# Main.net
KiCad netlist of a schematic drawn in Altium Designer
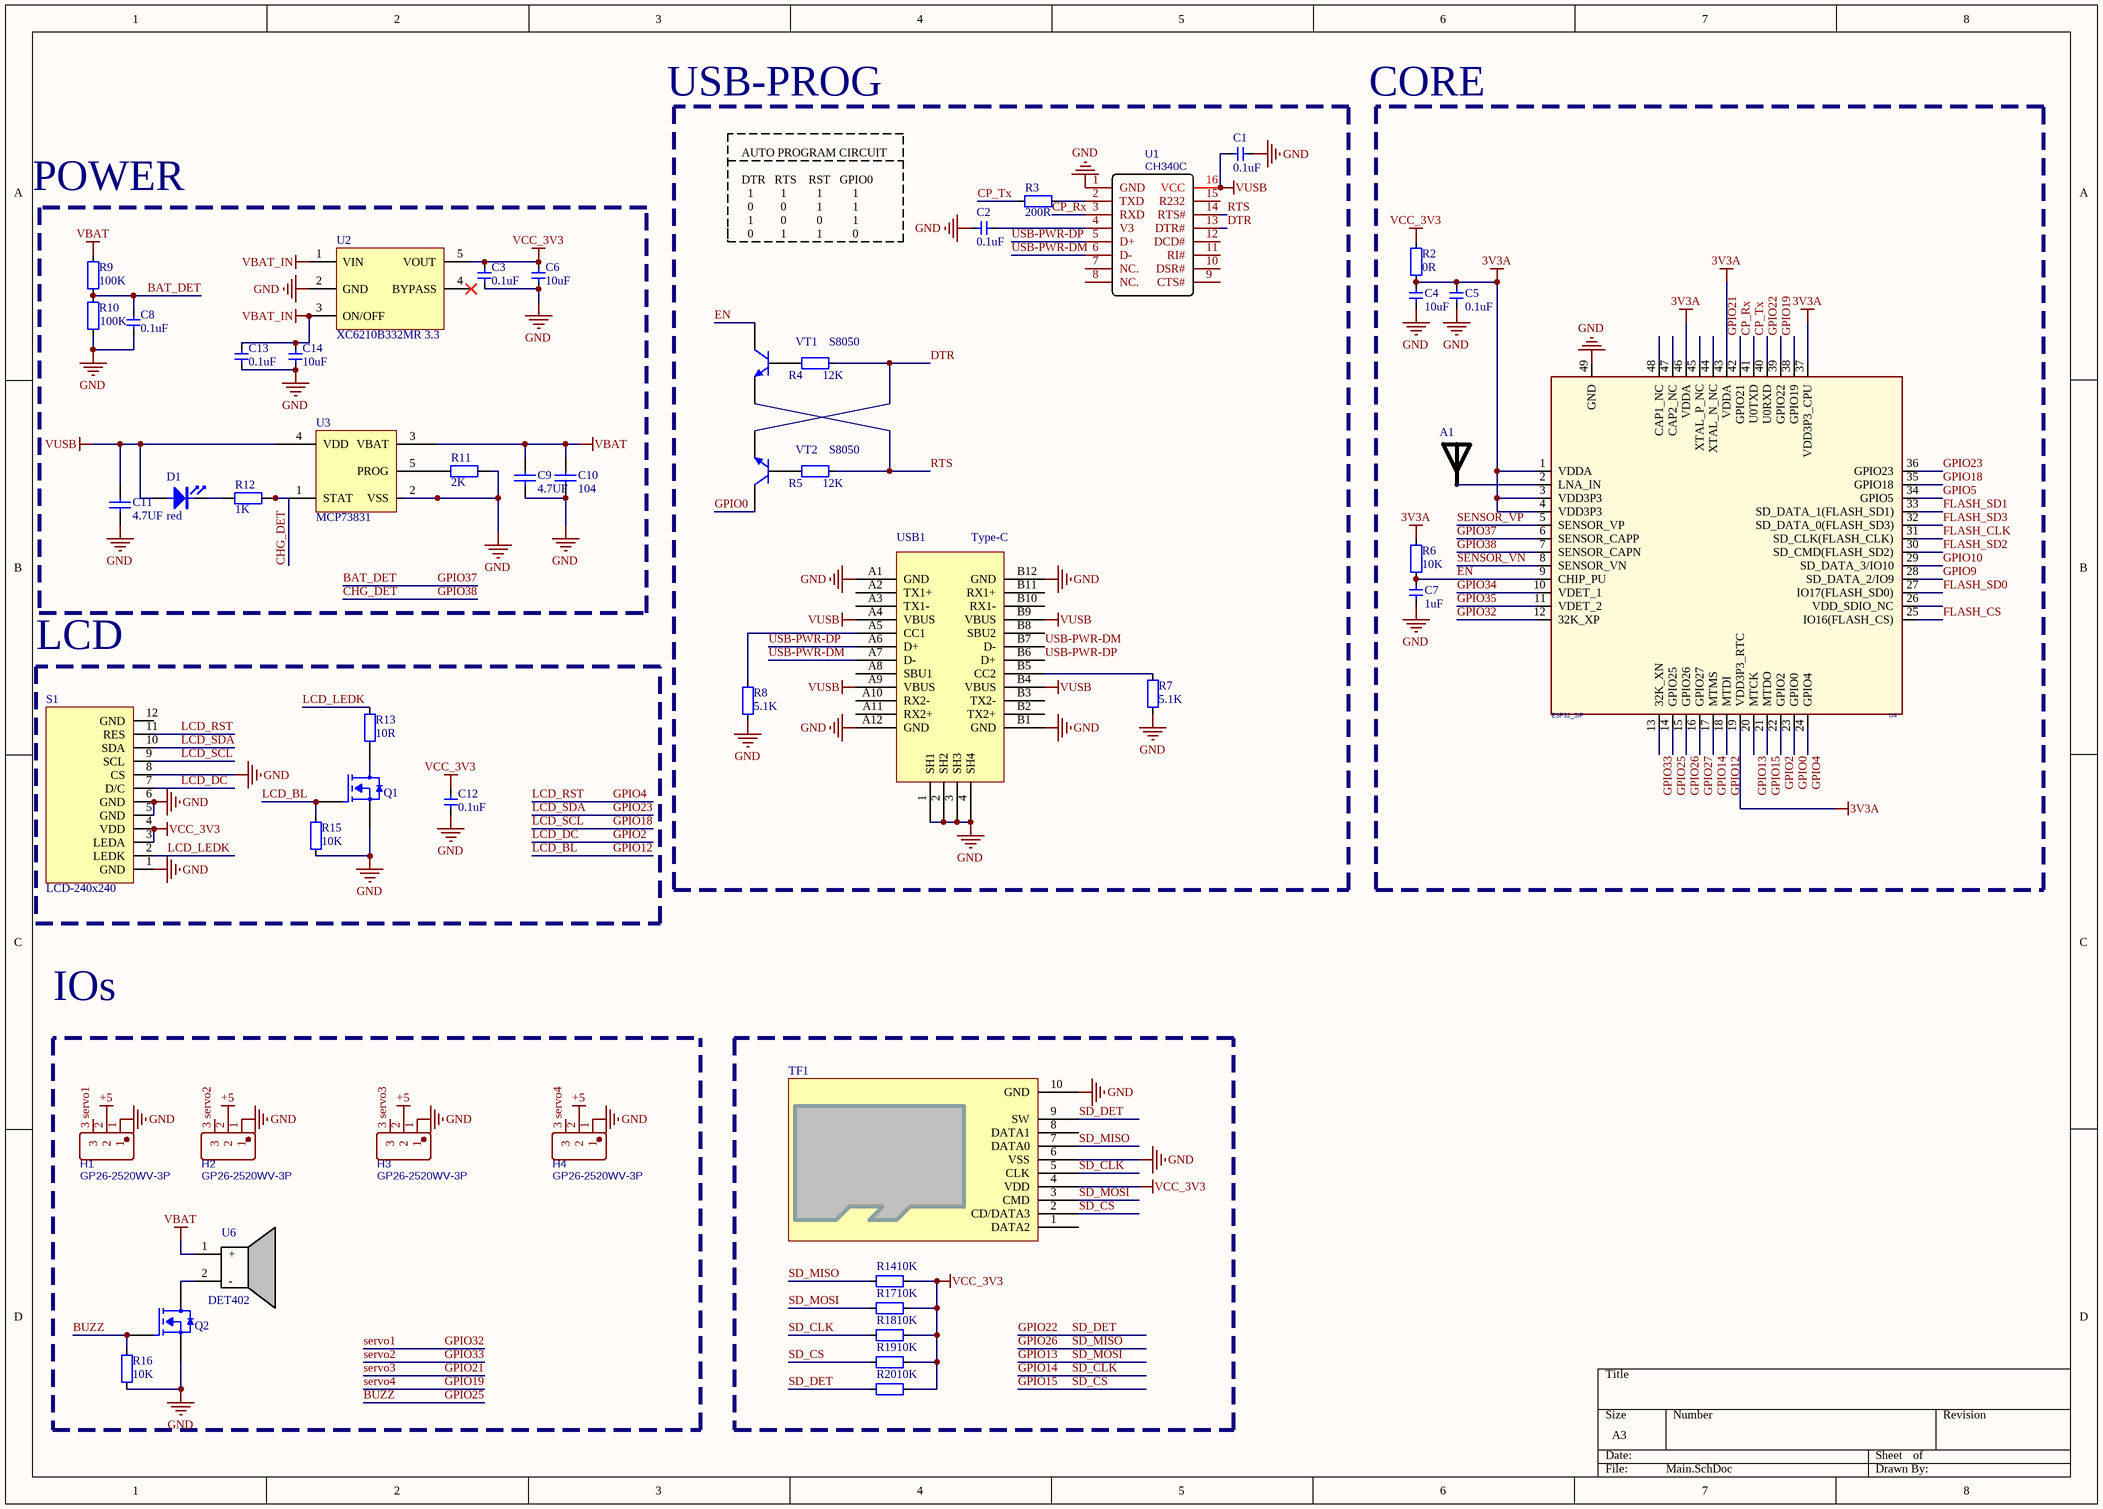
[diagram p0: Main.SchDoc]

(export (version "E")
  (design (tool "Eeschema 10.0.6"))
  (components
    (comp (ref "A1")
      (value "RAINSUN")
      (footprint "otto:ANT-Rainsun-AN5120")
      (libsource (lib "MyPcbLib") (part "ANT-Rainsun-AP5120"))
    )
    (comp (ref "C1")
      (value "0.1uF")
      (footprint "otto:C0603")
      (description "Capacitor")
      (libsource (lib "MyPcbLib") (part "电容-0402"))
    )
    (comp (ref "C2")
      (value "0.1uF")
      (footprint "otto:C0603")
      (description "Capacitor")
      (libsource (lib "MyPcbLib") (part "电容-0402"))
    )
    (comp (ref "C3")
      (value "0.1uF")
      (footprint "otto:C0603")
      (description "Capacitor")
      (libsource (lib "MyPcbLib") (part "电容-0402"))
    )
    (comp (ref "C4")
      (value "10uF")
      (footprint "otto:C0603")
      (description "Capacitor")
      (libsource (lib "MyPcbLib") (part "电容-0402"))
    )
    (comp (ref "C5")
      (value "0.1uF")
      (footprint "otto:C0603")
      (description "Capacitor")
      (libsource (lib "MyPcbLib") (part "电容-0402"))
    )
    (comp (ref "C6")
      (value "10uF")
      (footprint "otto:C0603")
      (description "Capacitor")
      (libsource (lib "MyPcbLib") (part "电容-0402"))
    )
    (comp (ref "C7")
      (value "1uF")
      (footprint "otto:C0603")
      (description "Capacitor")
      (libsource (lib "MyPcbLib") (part "电容-0402"))
    )
    (comp (ref "C8")
      (value "0.1uF")
      (footprint "C0603")
      (description "Capacitor")
      (libsource (lib "OTTO_ESP32") (part "电容-0402"))
    )
    (comp (ref "C9")
      (value "4.7UF")
      (footprint "C0603")
      (fields (field (name "C") "4.7UF"))
      (libsource (lib "元件库") (part "cap"))
    )
    (comp (ref "C10")
      (value "104")
      (footprint "otto:C0603")
      (fields (field (name "C") "104"))
      (libsource (lib "元件库") (part "cap"))
    )
    (comp (ref "C11")
      (value "4.7UF")
      (footprint "C0603")
      (fields (field (name "C") "4.7UF"))
      (libsource (lib "元件库") (part "cap"))
    )
    (comp (ref "C12")
      (value "0.1uF")
      (footprint "otto:C0603")
      (description "Capacitor")
      (libsource (lib "MyPcbLib") (part "电容-0402"))
    )
    (comp (ref "C13")
      (value "0.1uF")
      (footprint "otto:C0603")
      (description "Capacitor")
      (libsource (lib "MyPcbLib") (part "电容-0402"))
    )
    (comp (ref "C14")
      (value "10uF")
      (footprint "otto:C0603")
      (description "Capacitor")
      (libsource (lib "MyPcbLib") (part "电容-0402"))
    )
    (comp (ref "D1") (value "red") (footprint "LED0603") (libsource (lib "元件库") (part "LED")))
    (comp (ref "H1")
      (value "GP26-2520WV-3P")
      (footprint "otto:PIN2.54_1*3")
      (fields (field (name "BOM_SUPPLIER PART") "C2681738") (field (name "CONTRIBUTOR") "LCSC"))
      (libsource (lib "喷雾闹钟") (part "GP26-2520WV-3P"))
    )
    (comp (ref "H2")
      (value "GP26-2520WV-3P")
      (footprint "otto:PIN2.54_1*3")
      (fields (field (name "BOM_SUPPLIER PART") "C2681738") (field (name "CONTRIBUTOR") "LCSC"))
      (libsource (lib "喷雾闹钟") (part "GP26-2520WV-3P"))
    )
    (comp (ref "H3")
      (value "GP26-2520WV-3P")
      (footprint "otto:PIN2.54_1*3")
      (fields (field (name "BOM_SUPPLIER PART") "C2681738") (field (name "CONTRIBUTOR") "LCSC"))
      (libsource (lib "喷雾闹钟") (part "GP26-2520WV-3P"))
    )
    (comp (ref "H4")
      (value "GP26-2520WV-3P")
      (footprint "otto:PIN2.54_1*3")
      (fields (field (name "BOM_SUPPLIER PART") "C2681738") (field (name "CONTRIBUTOR") "LCSC"))
      (libsource (lib "喷雾闹钟") (part "GP26-2520WV-3P"))
    )
    (comp (ref "Q1")
      (value "AO3400A")
      (footprint "otto:SOT23-3")
      (description "N-MOS")
      (libsource (lib "MyPcbLib") (part "AO3400A"))
    )
    (comp (ref "Q2")
      (value "AO3400A")
      (footprint "otto:SOT23-3")
      (description "N-MOS")
      (libsource (lib "MyPcbLib") (part "AO3400A"))
    )
    (comp (ref "R2")
      (value "0R")
      (footprint "otto:R0603")
      (description "Resistor")
      (libsource (lib "OTTO_ESP32") (part "电阻-0402"))
    )
    (comp (ref "R3")
      (value "200R")
      (footprint "otto:R0603")
      (description "Resistor")
      (libsource (lib "") (part "电阻-0402_3"))
    )
    (comp (ref "R4")
      (value "12K")
      (footprint "otto:R0603")
      (description "Resistor")
      (libsource (lib "") (part "电阻-0402_2"))
    )
    (comp (ref "R5")
      (value "12K")
      (footprint "otto:R0603")
      (description "Resistor")
      (libsource (lib "") (part "电阻-0402_2"))
    )
    (comp (ref "R6")
      (value "10K")
      (footprint "otto:R0603")
      (description "Resistor")
      (libsource (lib "OTTO_ESP32") (part "电阻-0402"))
    )
    (comp (ref "R7")
      (value "5.1K")
      (footprint "otto:R0603")
      (description "Resistor")
      (libsource (lib "OTTO_ESP32") (part "电阻-0402"))
    )
    (comp (ref "R8")
      (value "5.1K")
      (footprint "otto:R0603")
      (description "Resistor")
      (libsource (lib "OTTO_ESP32") (part "电阻-0402"))
    )
    (comp (ref "R9")
      (value "100K")
      (footprint "otto:R0603")
      (description "Resistor")
      (libsource (lib "") (part "电阻-0402_1"))
    )
    (comp (ref "R10")
      (value "100K")
      (footprint "otto:R0603")
      (description "Resistor")
      (libsource (lib "") (part "电阻-0402_1"))
    )
    (comp (ref "R11")
      (value "2K")
      (footprint "otto:R0603")
      (fields (field (name "R") "2K"))
      (libsource (lib "OTTO_ESP32") (part "Res"))
    )
    (comp (ref "R12")
      (value "1K")
      (footprint "otto:R0603")
      (fields (field (name "R") "1K"))
      (libsource (lib "OTTO_ESP32") (part "Res"))
    )
    (comp (ref "R13")
      (value "10R")
      (footprint "otto:R0603")
      (description "Resistor")
      (libsource (lib "") (part "电阻-0402_1"))
    )
    (comp (ref "R14")
      (value "10K")
      (footprint "otto:R0603")
      (description "Resistor")
      (libsource (lib "") (part "电阻-0402_2"))
    )
    (comp (ref "R15")
      (value "10K")
      (footprint "otto:R0603")
      (description "Resistor")
      (libsource (lib "") (part "电阻-0402_1"))
    )
    (comp (ref "R16")
      (value "10K")
      (footprint "otto:R0603")
      (description "Resistor")
      (libsource (lib "") (part "电阻-0402_1"))
    )
    (comp (ref "R17")
      (value "10K")
      (footprint "otto:R0603")
      (description "Resistor")
      (libsource (lib "") (part "电阻-0402_2"))
    )
    (comp (ref "R18")
      (value "10K")
      (footprint "otto:R0603")
      (description "Resistor")
      (libsource (lib "") (part "电阻-0402_2"))
    )
    (comp (ref "R19")
      (value "10K")
      (footprint "otto:R0603")
      (description "Resistor")
      (libsource (lib "") (part "电阻-0402_2"))
    )
    (comp (ref "R20")
      (value "10K")
      (footprint "otto:R0603")
      (description "Resistor")
      (libsource (lib "") (part "电阻-0402_2"))
    )
    (comp (ref "S1")
      (value "LCD-240x240")
      (footprint "otto:LCD-240x240-FlUSH-154")
      (description "显示屏")
      (libsource (lib "mLib") (part "LCD-240x240"))
    )
    (comp (ref "TF1")
      (value "TF")
      (footprint "otto:TF-SOCKET")
      (description "8脚自弹")
      (libsource (lib "MyPcbLib") (part "TF卡座"))
    )
    (comp (ref "U1")
      (value "CH340C")
      (footprint "otto:SOP-16_L10.0-W3.9-P1.27-LS6.0-BL")
      (fields (field (name "BOM_SUPPLIER PART") "C84681"))
      (libsource (lib "altium-import") (part "root_0_CH340C_"))
    )
    (comp (ref "U2")
      (value "XC6210B332MR 3.3")
      (footprint "otto:SOT23-5")
      (description "LDO")
      (libsource (lib "mLib") (part "LP2992"))
    )
    (comp (ref "U3")
      (value "MCP73831")
      (footprint "otto:SOT23-5")
      (description "线性充电管理控制器")
      (libsource (lib "TriggersLib") (part "MCP73831"))
    )
    (comp (ref "U4")
      (value "ESP32_SIP")
      (footprint "QFN-48_7X7")
      (libsource (lib "mLib") (part "ESP32-PICO"))
    )
    (comp (ref "U6") (value "DET402") (footprint "otto:DET402") (libsource (lib "MyPcbLib") (part "DET402")))
    (comp (ref "USB1")
      (value "Type-C")
      (footprint "otto:Type-C-TOP")
      (libsource (lib "MyPcbLib") (part "USB-Type-C-TOP"))
    )
    (comp (ref "VT1")
      (value "S8050")
      (footprint "SOT23-3")
      (description "Surface mount NPN transistor, package SOT-23")
      (libsource (lib "MyPcbLib") (part "SMT_TRIODE_NPN"))
    )
    (comp (ref "VT2")
      (value "S8050")
      (footprint "SOT23-3")
      (description "Surface mount NPN transistor, package SOT-23")
      (libsource (lib "MyPcbLib") (part "SMT_TRIODE_NPN"))
    )
  )
  (nets
    (net (code "1") (name "+5") (class "Default")
      (node (ref "H1") (pin "2") (pinfunction "2_2") (pintype "passive"))
      (node (ref "H2") (pin "2") (pinfunction "2_2") (pintype "passive"))
      (node (ref "H3") (pin "2") (pinfunction "2_2") (pintype "passive"))
      (node (ref "H4") (pin "2") (pinfunction "2_2") (pintype "passive"))
    )
    (net (code "2") (name "/BAT_DET") (class "Default")
      (node (ref "C8") (pin "2") (pinfunction "2_2") (pintype "passive"))
      (node (ref "R10") (pin "2") (pinfunction "2_2") (pintype "passive"))
      (node (ref "R9") (pin "1") (pinfunction "1_1") (pintype "passive"))
      (node (ref "U4") (pin "6") (pinfunction "SENSOR_CAPP_6") (pintype "passive"))
    )
    (net (code "3") (name "/BUZZ") (class "Default")
      (node (ref "Q2") (pin "1") (pinfunction "G_1") (pintype "passive"))
      (node (ref "R16") (pin "2") (pinfunction "2_2") (pintype "passive"))
      (node (ref "U4") (pin "14") (pinfunction "GPIO25_14") (pintype "passive"))
    )
    (net (code "4") (name "/CHG_DET") (class "Default")
      (node (ref "R12") (pin "1") (pinfunction "1_1") (pintype "passive"))
      (node (ref "U3") (pin "1") (pinfunction "STAT_1") (pintype "passive"))
      (node (ref "U4") (pin "7") (pinfunction "SENSOR_CAPN_7") (pintype "passive"))
    )
    (net (code "5") (name "/CP_Rx") (class "Default")
      (node (ref "U1") (pin "3") (pinfunction "RXD_3") (pintype "passive"))
      (node (ref "U4") (pin "41") (pinfunction "U0TXD_41") (pintype "power_in"))
    )
    (net (code "6") (name "/CP_Tx") (class "Default")
      (node (ref "R3") (pin "1") (pinfunction "1_1") (pintype "passive"))
      (node (ref "U4") (pin "40") (pinfunction "U0RXD_40") (pintype "power_in"))
    )
    (net (code "7") (name "/DTR") (class "Default")
      (node (ref "R4") (pin "1") (pinfunction "1_1") (pintype "passive"))
      (node (ref "U1") (pin "13") (pinfunction "DTR#_13") (pintype "passive"))
      (node (ref "VT2") (pin "2") (pinfunction "E_2") (pintype "passive"))
    )
    (net (code "8") (name "/EN") (class "Default")
      (node (ref "C7") (pin "1") (pinfunction "1_1") (pintype "passive"))
      (node (ref "R6") (pin "2") (pinfunction "2_2") (pintype "passive"))
      (node (ref "U4") (pin "9") (pinfunction "CHIP_PU_9") (pintype "passive"))
      (node (ref "VT1") (pin "3") (pinfunction "C_3") (pintype "passive"))
    )
    (net (code "9") (name "/FLASH_CLK") (class "Default")
      (node (ref "U4") (pin "31") (pinfunction "SD_CLK(FLASH_CLK)_31") (pintype "passive"))
    )
    (net (code "10") (name "/FLASH_CS") (class "Default")
      (node (ref "U4") (pin "25") (pinfunction "IO16(FLASH_CS)_25") (pintype "passive"))
    )
    (net (code "11") (name "/FLASH_SD0") (class "Default")
      (node (ref "U4") (pin "27") (pinfunction "IO17(FLASH_SD0)_27") (pintype "passive"))
    )
    (net (code "12") (name "/FLASH_SD1") (class "Default")
      (node (ref "U4") (pin "33") (pinfunction "SD_DATA_1(FLASH_SD1)_33") (pintype "passive"))
    )
    (net (code "13") (name "/FLASH_SD2") (class "Default")
      (node (ref "U4") (pin "30") (pinfunction "SD_CMD(FLASH_SD2)_30") (pintype "passive"))
    )
    (net (code "14") (name "/FLASH_SD3") (class "Default")
      (node (ref "U4") (pin "32") (pinfunction "SD_DATA_0(FLASH_SD3)_32") (pintype "passive"))
    )
    (net (code "15") (name "/GPIO0") (class "Default")
      (node (ref "U4") (pin "23") (pinfunction "GPIO0_23") (pintype "passive"))
      (node (ref "VT2") (pin "3") (pinfunction "C_3") (pintype "passive"))
    )
    (net (code "16") (name "/GPIO2") (class "Default")
      (node (ref "S1") (pin "7") (pinfunction "D/C_7") (pintype "passive"))
      (node (ref "U4") (pin "22") (pinfunction "GPIO2_22") (pintype "passive"))
    )
    (net (code "17") (name "/GPIO4") (class "Default")
      (node (ref "S1") (pin "11") (pinfunction "RES_11") (pintype "passive"))
      (node (ref "U4") (pin "24") (pinfunction "GPIO4_24") (pintype "passive"))
    )
    (net (code "18") (name "/GPIO5") (class "Default")
      (node (ref "U4") (pin "34") (pinfunction "GPIO5_34") (pintype "passive"))
    )
    (net (code "19") (name "/GPIO9") (class "Default")
      (node (ref "U4") (pin "28") (pinfunction "SD_DATA_2/IO9_28") (pintype "passive"))
    )
    (net (code "20") (name "/GPIO10") (class "Default")
      (node (ref "U4") (pin "29") (pinfunction "SD_DATA_3/IO10_29") (pintype "passive"))
    )
    (net (code "21") (name "/GPIO12") (class "Default")
      (node (ref "Q1") (pin "1") (pinfunction "G_1") (pintype "passive"))
      (node (ref "R15") (pin "2") (pinfunction "2_2") (pintype "passive"))
      (node (ref "U4") (pin "18") (pinfunction "MTDI_18") (pintype "passive"))
    )
    (net (code "22") (name "/GPIO13") (class "Default")
      (node (ref "R17") (pin "2") (pinfunction "2_2") (pintype "passive"))
      (node (ref "TF1") (pin "3") (pinfunction "CMD_3") (pintype "passive"))
      (node (ref "U4") (pin "20") (pinfunction "MTCK_20") (pintype "passive"))
    )
    (net (code "23") (name "/GPIO14") (class "Default")
      (node (ref "R18") (pin "2") (pinfunction "2_2") (pintype "passive"))
      (node (ref "TF1") (pin "5") (pinfunction "CLK_5") (pintype "passive"))
      (node (ref "U4") (pin "17") (pinfunction "MTMS_17") (pintype "passive"))
    )
    (net (code "24") (name "/GPIO15") (class "Default")
      (node (ref "R19") (pin "2") (pinfunction "2_2") (pintype "passive"))
      (node (ref "TF1") (pin "2") (pinfunction "CD/DATA3_2") (pintype "passive"))
      (node (ref "U4") (pin "21") (pinfunction "MTDO_21") (pintype "passive"))
    )
    (net (code "25") (name "/GPIO18") (class "Default")
      (node (ref "S1") (pin "9") (pinfunction "SCL_9") (pintype "passive"))
      (node (ref "U4") (pin "35") (pinfunction "GPIO18_35") (pintype "passive"))
    )
    (net (code "26") (name "/GPIO19") (class "Default")
      (node (ref "H4") (pin "3") (pinfunction "3_3") (pintype "passive"))
      (node (ref "U4") (pin "38") (pinfunction "GPIO19_38") (pintype "passive"))
    )
    (net (code "27") (name "/GPIO21") (class "Default")
      (node (ref "H3") (pin "3") (pinfunction "3_3") (pintype "passive"))
      (node (ref "U4") (pin "42") (pinfunction "GPIO21_42") (pintype "passive"))
    )
    (net (code "28") (name "/GPIO22") (class "Default")
      (node (ref "R20") (pin "2") (pinfunction "2_2") (pintype "passive"))
      (node (ref "TF1") (pin "9") (pinfunction "SW_9") (pintype "passive"))
      (node (ref "U4") (pin "39") (pinfunction "GPIO22_39") (pintype "passive"))
    )
    (net (code "29") (name "/GPIO23") (class "Default")
      (node (ref "S1") (pin "10") (pinfunction "SDA_10") (pintype "passive"))
      (node (ref "U4") (pin "36") (pinfunction "GPIO23_36") (pintype "passive"))
    )
    (net (code "30") (name "/GPIO26") (class "Default")
      (node (ref "R14") (pin "2") (pinfunction "2_2") (pintype "passive"))
      (node (ref "TF1") (pin "7") (pinfunction "DATA0_7") (pintype "passive"))
      (node (ref "U4") (pin "15") (pinfunction "GPIO26_15") (pintype "passive"))
    )
    (net (code "31") (name "/GPIO27") (class "Default")
      (node (ref "U4") (pin "16") (pinfunction "GPIO27_16") (pintype "passive"))
    )
    (net (code "32") (name "/GPIO32") (class "Default")
      (node (ref "H1") (pin "3") (pinfunction "3_3") (pintype "passive"))
      (node (ref "U4") (pin "12") (pinfunction "32K_XP_12") (pintype "passive"))
    )
    (net (code "33") (name "/GPIO33") (class "Default")
      (node (ref "H2") (pin "3") (pinfunction "3_3") (pintype "passive"))
      (node (ref "U4") (pin "13") (pinfunction "32K_XN_13") (pintype "passive"))
    )
    (net (code "34") (name "/GPIO34") (class "Default")
      (node (ref "U4") (pin "10") (pinfunction "VDET_1_10") (pintype "passive"))
    )
    (net (code "35") (name "/GPIO35") (class "Default")
      (node (ref "U4") (pin "11") (pinfunction "VDET_2_11") (pintype "passive"))
    )
    (net (code "36") (name "/LCD_LEDK") (class "Default")
      (node (ref "R13") (pin "2") (pinfunction "2_2") (pintype "passive"))
      (node (ref "S1") (pin "2") (pinfunction "LEDK_2") (pintype "passive"))
    )
    (net (code "37") (name "/RTS") (class "Default")
      (node (ref "R5") (pin "1") (pinfunction "1_1") (pintype "passive"))
      (node (ref "U1") (pin "14") (pinfunction "RTS#_14") (pintype "passive"))
      (node (ref "VT1") (pin "2") (pinfunction "E_2") (pintype "passive"))
    )
    (net (code "38") (name "/SENSOR_VN") (class "Default")
      (node (ref "U4") (pin "8") (pinfunction "SENSOR_VN_8") (pintype "passive"))
    )
    (net (code "39") (name "/SENSOR_VP") (class "Default")
      (node (ref "U4") (pin "5") (pinfunction "SENSOR_VP_5") (pintype "passive"))
    )
    (net (code "40") (name "/USB-PWR-DM") (class "Default")
      (node (ref "U1") (pin "6") (pinfunction "D-_6") (pintype "passive"))
      (node (ref "USB1") (pin "A7") (pinfunction "D-_A7") (pintype "passive"))
      (node (ref "USB1") (pin "B7") (pinfunction "D-_B7") (pintype "passive"))
    )
    (net (code "41") (name "/USB-PWR-DP") (class "Default")
      (node (ref "U1") (pin "5") (pinfunction "D+_5") (pintype "passive"))
      (node (ref "USB1") (pin "A6") (pinfunction "D+_A6") (pintype "passive"))
      (node (ref "USB1") (pin "B6") (pinfunction "D+_B6") (pintype "passive"))
    )
    (net (code "42") (name "3V3A") (class "Default")
      (node (ref "C4") (pin "2") (pinfunction "2_2") (pintype "passive"))
      (node (ref "C5") (pin "2") (pinfunction "2_2") (pintype "passive"))
      (node (ref "R2") (pin "2") (pinfunction "2_2") (pintype "passive"))
      (node (ref "R6") (pin "1") (pinfunction "1_1") (pintype "passive"))
      (node (ref "U4") (pin "1") (pinfunction "VDDA_1") (pintype "power_in"))
      (node (ref "U4") (pin "19") (pinfunction "VDD3P3_RTC_19") (pintype "power_in"))
      (node (ref "U4") (pin "3") (pinfunction "VDD3P3_3") (pintype "power_in"))
      (node (ref "U4") (pin "37") (pinfunction "VDD3P3_CPU_37") (pintype "power_in"))
      (node (ref "U4") (pin "4") (pinfunction "VDD3P3_4") (pintype "power_in"))
      (node (ref "U4") (pin "43") (pinfunction "VDDA_43") (pintype "power_in"))
      (node (ref "U4") (pin "46") (pinfunction "VDDA_46") (pintype "power_in"))
    )
    (net (code "43") (name "GND") (class "Default")
      (node (ref "C1") (pin "1") (pinfunction "1_1") (pintype "passive"))
      (node (ref "C10") (pin "2") (pinfunction "2_2") (pintype "passive"))
      (node (ref "C11") (pin "1") (pinfunction "1_1") (pintype "passive"))
      (node (ref "C12") (pin "1") (pinfunction "1_1") (pintype "passive"))
      (node (ref "C13") (pin "1") (pinfunction "1_1") (pintype "passive"))
      (node (ref "C14") (pin "1") (pinfunction "1_1") (pintype "passive"))
      (node (ref "C2") (pin "2") (pinfunction "2_2") (pintype "passive"))
      (node (ref "C3") (pin "1") (pinfunction "1_1") (pintype "passive"))
      (node (ref "C4") (pin "1") (pinfunction "1_1") (pintype "passive"))
      (node (ref "C5") (pin "1") (pinfunction "1_1") (pintype "passive"))
      (node (ref "C6") (pin "1") (pinfunction "1_1") (pintype "passive"))
      (node (ref "C7") (pin "2") (pinfunction "2_2") (pintype "passive"))
      (node (ref "C8") (pin "1") (pinfunction "1_1") (pintype "passive"))
      (node (ref "C9") (pin "1") (pinfunction "1_1") (pintype "passive"))
      (node (ref "H1") (pin "1") (pinfunction "1_1") (pintype "passive"))
      (node (ref "H2") (pin "1") (pinfunction "1_1") (pintype "passive"))
      (node (ref "H3") (pin "1") (pinfunction "1_1") (pintype "passive"))
      (node (ref "H4") (pin "1") (pinfunction "1_1") (pintype "passive"))
      (node (ref "Q1") (pin "2") (pinfunction "S_2") (pintype "passive"))
      (node (ref "Q2") (pin "2") (pinfunction "S_2") (pintype "passive"))
      (node (ref "R10") (pin "1") (pinfunction "1_1") (pintype "passive"))
      (node (ref "R11") (pin "1") (pinfunction "1_1") (pintype "passive"))
      (node (ref "R15") (pin "1") (pinfunction "1_1") (pintype "passive"))
      (node (ref "R16") (pin "1") (pinfunction "1_1") (pintype "passive"))
      (node (ref "R7") (pin "2") (pinfunction "2_2") (pintype "passive"))
      (node (ref "R8") (pin "2") (pinfunction "2_2") (pintype "passive"))
      (node (ref "S1") (pin "1") (pinfunction "GND_1") (pintype "passive"))
      (node (ref "S1") (pin "5") (pinfunction "GND_5") (pintype "passive"))
      (node (ref "S1") (pin "6") (pinfunction "GND_6") (pintype "passive"))
      (node (ref "S1") (pin "8") (pinfunction "CS_8") (pintype "passive"))
      (node (ref "TF1") (pin "10") (pinfunction "GND_10") (pintype "passive"))
      (node (ref "TF1") (pin "6") (pinfunction "VSS_6") (pintype "passive"))
      (node (ref "U1") (pin "1") (pinfunction "GND_1") (pintype "passive"))
      (node (ref "U2") (pin "2") (pinfunction "GND_2") (pintype "passive"))
      (node (ref "U3") (pin "2") (pinfunction "VSS_2") (pintype "passive"))
      (node (ref "U4") (pin "49") (pinfunction "GND_49") (pintype "power_in"))
      (node (ref "USB1") (pin "1") (pinfunction "SH1_1") (pintype "passive"))
      (node (ref "USB1") (pin "2") (pinfunction "SH2_2") (pintype "passive"))
      (node (ref "USB1") (pin "3") (pinfunction "SH3_3") (pintype "passive"))
      (node (ref "USB1") (pin "4") (pinfunction "SH4_4") (pintype "passive"))
      (node (ref "USB1") (pin "A1") (pinfunction "GND_A1") (pintype "passive"))
      (node (ref "USB1") (pin "A12") (pinfunction "GND_A12") (pintype "passive"))
      (node (ref "USB1") (pin "B1") (pinfunction "GND_B1") (pintype "passive"))
      (node (ref "USB1") (pin "B12") (pinfunction "GND_B12") (pintype "passive"))
    )
    (net (code "44") (name "Net-(D1-PadK)") (class "Default")
      (node (ref "D1") (pin "K") (pinfunction "K_K") (pintype "passive"))
      (node (ref "R12") (pin "2") (pinfunction "2_2") (pintype "passive"))
    )
    (net (code "45") (name "Net-(Q1-D)") (class "Default")
      (node (ref "Q1") (pin "3") (pinfunction "D_3") (pintype "passive"))
      (node (ref "R13") (pin "1") (pinfunction "1_1") (pintype "passive"))
    )
    (net (code "46") (name "Net-(Q2-D)") (class "Default")
      (node (ref "Q2") (pin "3") (pinfunction "D_3") (pintype "passive"))
      (node (ref "U6") (pin "2") (pinfunction "-_2") (pintype "passive"))
    )
    (net (code "47") (name "Net-(U1-TXD)") (class "Default")
      (node (ref "R3") (pin "2") (pinfunction "2_2") (pintype "passive"))
      (node (ref "U1") (pin "2") (pinfunction "TXD_2") (pintype "passive"))
    )
    (net (code "48") (name "Net-(U1-V3)") (class "Default")
      (node (ref "C2") (pin "1") (pinfunction "1_1") (pintype "passive"))
      (node (ref "U1") (pin "4") (pinfunction "V3_4") (pintype "passive"))
    )
    (net (code "49") (name "Net-(U3-PROG)") (class "Default")
      (node (ref "R11") (pin "2") (pinfunction "2_2") (pintype "passive"))
      (node (ref "U3") (pin "5") (pinfunction "PROG_5") (pintype "passive"))
    )
    (net (code "50") (name "Net-(U4-LNA_IN)") (class "Default")
      (node (ref "A1") (pin "1") (pinfunction "1_1") (pintype "passive"))
      (node (ref "U4") (pin "2") (pinfunction "LNA_IN_2") (pintype "passive"))
    )
    (net (code "51") (name "Net-(USB1-CC1)") (class "Default")
      (node (ref "R8") (pin "1") (pinfunction "1_1") (pintype "passive"))
      (node (ref "USB1") (pin "A5") (pinfunction "CC1_A5") (pintype "passive"))
    )
    (net (code "52") (name "Net-(USB1-CC2)") (class "Default")
      (node (ref "R7") (pin "1") (pinfunction "1_1") (pintype "passive"))
      (node (ref "USB1") (pin "B5") (pinfunction "CC2_B5") (pintype "passive"))
    )
    (net (code "53") (name "Net-(VT1-B)") (class "Default")
      (node (ref "R4") (pin "2") (pinfunction "2_2") (pintype "passive"))
      (node (ref "VT1") (pin "1") (pinfunction "B_1") (pintype "passive"))
    )
    (net (code "54") (name "Net-(VT2-B)") (class "Default")
      (node (ref "R5") (pin "2") (pinfunction "2_2") (pintype "passive"))
      (node (ref "VT2") (pin "1") (pinfunction "B_1") (pintype "passive"))
    )
    (net (code "55") (name "VBAT") (class "Default")
      (node (ref "C10") (pin "1") (pinfunction "1_1") (pintype "passive"))
      (node (ref "C9") (pin "2") (pinfunction "2_2") (pintype "passive"))
      (node (ref "R9") (pin "2") (pinfunction "2_2") (pintype "passive"))
      (node (ref "U3") (pin "3") (pinfunction "VBAT_3") (pintype "passive"))
      (node (ref "U6") (pin "1") (pinfunction "+_1") (pintype "passive"))
    )
    (net (code "56") (name "VBAT_IN") (class "Default")
      (node (ref "C13") (pin "2") (pinfunction "2_2") (pintype "passive"))
      (node (ref "C14") (pin "2") (pinfunction "2_2") (pintype "passive"))
      (node (ref "U2") (pin "1") (pinfunction "VIN_1") (pintype "passive"))
      (node (ref "U2") (pin "3") (pinfunction "ON/OFF_3") (pintype "passive"))
    )
    (net (code "57") (name "VCC_3V3") (class "Default")
      (node (ref "C12") (pin "2") (pinfunction "2_2") (pintype "passive"))
      (node (ref "C3") (pin "2") (pinfunction "2_2") (pintype "passive"))
      (node (ref "C6") (pin "2") (pinfunction "2_2") (pintype "passive"))
      (node (ref "R14") (pin "1") (pinfunction "1_1") (pintype "passive"))
      (node (ref "R17") (pin "1") (pinfunction "1_1") (pintype "passive"))
      (node (ref "R18") (pin "1") (pinfunction "1_1") (pintype "passive"))
      (node (ref "R19") (pin "1") (pinfunction "1_1") (pintype "passive"))
      (node (ref "R2") (pin "1") (pinfunction "1_1") (pintype "passive"))
      (node (ref "R20") (pin "1") (pinfunction "1_1") (pintype "passive"))
      (node (ref "S1") (pin "3") (pinfunction "LEDA_3") (pintype "passive"))
      (node (ref "S1") (pin "4") (pinfunction "VDD_4") (pintype "passive"))
      (node (ref "TF1") (pin "4") (pinfunction "VDD_4") (pintype "passive"))
      (node (ref "U2") (pin "5") (pinfunction "VOUT_5") (pintype "passive"))
    )
    (net (code "58") (name "VUSB") (class "Default")
      (node (ref "C1") (pin "2") (pinfunction "2_2") (pintype "passive"))
      (node (ref "C11") (pin "2") (pinfunction "2_2") (pintype "passive"))
      (node (ref "D1") (pin "A") (pinfunction "A_A") (pintype "passive"))
      (node (ref "U1") (pin "16") (pinfunction "VCC_16") (pintype "passive"))
      (node (ref "U3") (pin "4") (pinfunction "VDD_4") (pintype "passive"))
      (node (ref "USB1") (pin "A4") (pinfunction "VBUS_A4") (pintype "passive"))
      (node (ref "USB1") (pin "A9") (pinfunction "VBUS_A9") (pintype "passive"))
      (node (ref "USB1") (pin "B4") (pinfunction "VBUS_B4") (pintype "passive"))
      (node (ref "USB1") (pin "B9") (pinfunction "VBUS_B9") (pintype "passive"))
    )
    (net (code "59") (name "unconnected-(S1-GND-Pad12)") (class "Default")
      (node (ref "S1") (pin "12") (pinfunction "GND_12") (pintype "passive"))
    )
    (net (code "60") (name "unconnected-(TF1-DATA1-Pad8)") (class "Default")
      (node (ref "TF1") (pin "8") (pinfunction "DATA1_8") (pintype "passive"))
    )
    (net (code "61") (name "unconnected-(TF1-DATA2-Pad1)") (class "Default")
      (node (ref "TF1") (pin "1") (pinfunction "DATA2_1") (pintype "passive"))
    )
    (net (code "62") (name "unconnected-(U1-CTS#-Pad9)") (class "Default")
      (node (ref "U1") (pin "9") (pinfunction "CTS#_9") (pintype "passive"))
    )
    (net (code "63") (name "unconnected-(U1-DCD#-Pad12)") (class "Default")
      (node (ref "U1") (pin "12") (pinfunction "DCD#_12") (pintype "passive"))
    )
    (net (code "64") (name "unconnected-(U1-DSR#-Pad10)") (class "Default")
      (node (ref "U1") (pin "10") (pinfunction "DSR#_10") (pintype "passive"))
    )
    (net (code "65") (name "unconnected-(U1-NC.-Pad7)") (class "Default")
      (node (ref "U1") (pin "7") (pinfunction "NC._7") (pintype "passive"))
    )
    (net (code "66") (name "unconnected-(U1-NC.-Pad8)") (class "Default")
      (node (ref "U1") (pin "8") (pinfunction "NC._8") (pintype "passive"))
    )
    (net (code "67") (name "unconnected-(U1-R232-Pad15)") (class "Default")
      (node (ref "U1") (pin "15") (pinfunction "R232_15") (pintype "passive"))
    )
    (net (code "68") (name "unconnected-(U1-RI#-Pad11)") (class "Default")
      (node (ref "U1") (pin "11") (pinfunction "RI#_11") (pintype "passive"))
    )
    (net (code "69") (name "unconnected-(U2-BYPASS-Pad4)") (class "Default")
      (node (ref "U2") (pin "4") (pinfunction "BYPASS_4") (pintype "passive+no_connect"))
    )
    (net (code "70") (name "unconnected-(U4-CAP1_NC-Pad48)") (class "Default")
      (node (ref "U4") (pin "48") (pinfunction "CAP1_NC_48") (pintype "passive"))
    )
    (net (code "71") (name "unconnected-(U4-CAP2_NC-Pad47)") (class "Default")
      (node (ref "U4") (pin "47") (pinfunction "CAP2_NC_47") (pintype "passive"))
    )
    (net (code "72") (name "unconnected-(U4-VDD_SDIO_NC-Pad26)") (class "Default")
      (node (ref "U4") (pin "26") (pinfunction "VDD_SDIO_NC_26") (pintype "passive"))
    )
    (net (code "73") (name "unconnected-(U4-XTAL_N_NC-Pad44)") (class "Default")
      (node (ref "U4") (pin "44") (pinfunction "XTAL_N_NC_44") (pintype "passive"))
    )
    (net (code "74") (name "unconnected-(U4-XTAL_P_NC-Pad45)") (class "Default")
      (node (ref "U4") (pin "45") (pinfunction "XTAL_P_NC_45") (pintype "passive"))
    )
    (net (code "75") (name "unconnected-(USB1-RX1+-PadB11)") (class "Default")
      (node (ref "USB1") (pin "B11") (pinfunction "RX1+_B11") (pintype "passive"))
    )
    (net (code "76") (name "unconnected-(USB1-RX1--PadB10)") (class "Default")
      (node (ref "USB1") (pin "B10") (pinfunction "RX1-_B10") (pintype "passive"))
    )
    (net (code "77") (name "unconnected-(USB1-RX2+-PadA11)") (class "Default")
      (node (ref "USB1") (pin "A11") (pinfunction "RX2+_A11") (pintype "passive"))
    )
    (net (code "78") (name "unconnected-(USB1-RX2--PadA10)") (class "Default")
      (node (ref "USB1") (pin "A10") (pinfunction "RX2-_A10") (pintype "passive"))
    )
    (net (code "79") (name "unconnected-(USB1-SBU1-PadA8)") (class "Default")
      (node (ref "USB1") (pin "A8") (pinfunction "SBU1_A8") (pintype "passive"))
    )
    (net (code "80") (name "unconnected-(USB1-SBU2-PadB8)") (class "Default")
      (node (ref "USB1") (pin "B8") (pinfunction "SBU2_B8") (pintype "passive"))
    )
    (net (code "81") (name "unconnected-(USB1-TX1+-PadA2)") (class "Default")
      (node (ref "USB1") (pin "A2") (pinfunction "TX1+_A2") (pintype "passive"))
    )
    (net (code "82") (name "unconnected-(USB1-TX1--PadA3)") (class "Default")
      (node (ref "USB1") (pin "A3") (pinfunction "TX1-_A3") (pintype "passive"))
    )
    (net (code "83") (name "unconnected-(USB1-TX2+-PadB2)") (class "Default")
      (node (ref "USB1") (pin "B2") (pinfunction "TX2+_B2") (pintype "passive"))
    )
    (net (code "84") (name "unconnected-(USB1-TX2--PadB3)") (class "Default")
      (node (ref "USB1") (pin "B3") (pinfunction "TX2-_B3") (pintype "passive"))
    )
  )
)
